# SD_Card_Board.net
KiCad netlist of a schematic drawn in EAGLE
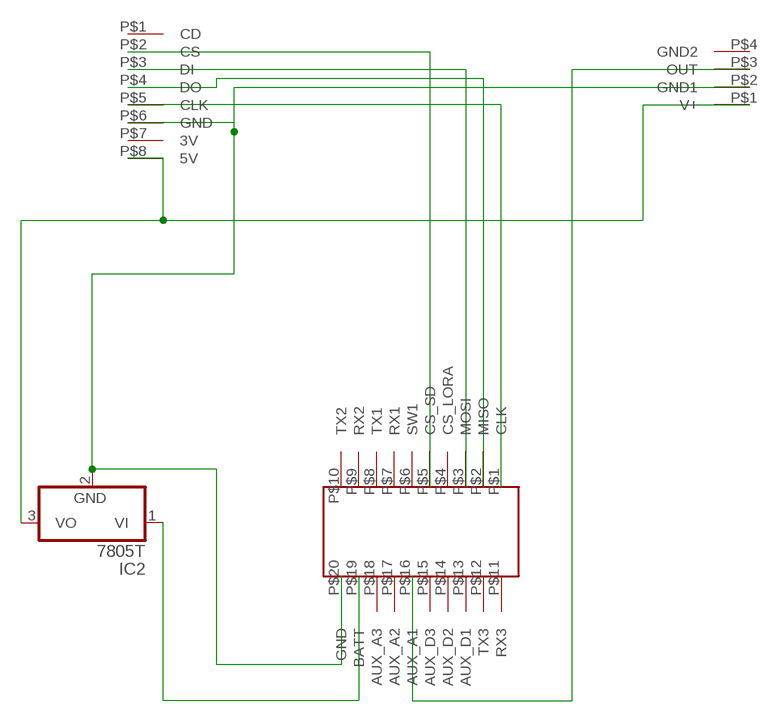
[diagram p0: schematic, sheet 1]

(export (version "E")
  (design (tool "Eeschema 10.0.6"))
  (components
    (comp (ref "IC2")
      (value "7805T")
      (footprint "eagle-import:TO220H")
      (libsource (lib "eagle-import") (part "78T05"))
    )
    (comp (ref "U$1")
      (value "SMALLHEADERPACKAGE")
      (footprint "eagle-import:SMALLHEADERPACKAGE")
      (libsource (lib "eagle-import") (part "SMALLHEADERPACKAGE"))
    )
    (comp (ref "U$2")
      (value "SDCARDREADER")
      (footprint "eagle-import:SDCARDBOARD")
      (libsource (lib "eagle-import") (part "SDCARDREADER"))
    )
    (comp (ref "U$3")
      (value "THERMOCOUPLE")
      (footprint "eagle-import:THERMOBOARD")
      (libsource (lib "eagle-import") (part "THERMOCOUPLE"))
    )
  )
  (nets
    (net (code "1") (name "Net-(IC2-GND)") (class "Default")
      (node (ref "IC2") (pin "2") (pinfunction "GND_2") (pintype "passive"))
      (node (ref "U$1") (pin "P$20") (pinfunction "GND_P$20") (pintype "bidirectional"))
      (node (ref "U$2") (pin "P$6") (pinfunction "GND_P$6") (pintype "bidirectional"))
      (node (ref "U$3") (pin "P$2") (pinfunction "GND1_P$2") (pintype "bidirectional"))
    )
    (net (code "2") (name "Net-(IC2-VI)") (class "Default")
      (node (ref "IC2") (pin "1") (pinfunction "VI_1") (pintype "input"))
      (node (ref "U$1") (pin "P$19") (pinfunction "BATT_P$19") (pintype "bidirectional"))
    )
    (net (code "3") (name "Net-(IC2-VO)") (class "Default")
      (node (ref "IC2") (pin "3") (pinfunction "VO_3") (pintype "passive"))
      (node (ref "U$2") (pin "P$8") (pinfunction "5V_P$8") (pintype "bidirectional"))
      (node (ref "U$3") (pin "P$1") (pinfunction "V+_P$1") (pintype "bidirectional"))
    )
    (net (code "4") (name "Net-(U$1-AUX_A1)") (class "Default")
      (node (ref "U$1") (pin "P$16") (pinfunction "AUX_A1_P$16") (pintype "bidirectional"))
      (node (ref "U$3") (pin "P$3") (pinfunction "OUT_P$3") (pintype "bidirectional"))
    )
    (net (code "5") (name "Net-(U$1-CLK)") (class "Default")
      (node (ref "U$1") (pin "P$1") (pinfunction "CLK_P$1") (pintype "bidirectional"))
      (node (ref "U$2") (pin "P$5") (pinfunction "CLK_P$5") (pintype "bidirectional"))
    )
    (net (code "6") (name "Net-(U$1-CS_SD)") (class "Default")
      (node (ref "U$1") (pin "P$5") (pinfunction "CS_SD_P$5") (pintype "bidirectional"))
      (node (ref "U$2") (pin "P$2") (pinfunction "CS_P$2") (pintype "bidirectional"))
    )
    (net (code "7") (name "Net-(U$1-MISO)") (class "Default")
      (node (ref "U$1") (pin "P$2") (pinfunction "MISO_P$2") (pintype "bidirectional"))
      (node (ref "U$2") (pin "P$4") (pinfunction "DO_P$4") (pintype "bidirectional"))
    )
    (net (code "8") (name "Net-(U$1-MOSI)") (class "Default")
      (node (ref "U$1") (pin "P$3") (pinfunction "MOSI_P$3") (pintype "bidirectional"))
      (node (ref "U$2") (pin "P$3") (pinfunction "DI_P$3") (pintype "bidirectional"))
    )
    (net (code "9") (name "unconnected-(U$1-AUX_A2-PadP$17)") (class "Default")
      (node (ref "U$1") (pin "P$17") (pinfunction "AUX_A2_P$17") (pintype "bidirectional"))
    )
    (net (code "10") (name "unconnected-(U$1-AUX_A3-PadP$18)") (class "Default")
      (node (ref "U$1") (pin "P$18") (pinfunction "AUX_A3_P$18") (pintype "bidirectional"))
    )
    (net (code "11") (name "unconnected-(U$1-AUX_D1-PadP$13)") (class "Default")
      (node (ref "U$1") (pin "P$13") (pinfunction "AUX_D1_P$13") (pintype "bidirectional"))
    )
    (net (code "12") (name "unconnected-(U$1-AUX_D2-PadP$14)") (class "Default")
      (node (ref "U$1") (pin "P$14") (pinfunction "AUX_D2_P$14") (pintype "bidirectional"))
    )
    (net (code "13") (name "unconnected-(U$1-AUX_D3-PadP$15)") (class "Default")
      (node (ref "U$1") (pin "P$15") (pinfunction "AUX_D3_P$15") (pintype "bidirectional"))
    )
    (net (code "14") (name "unconnected-(U$1-CS_LORA-PadP$4)") (class "Default")
      (node (ref "U$1") (pin "P$4") (pinfunction "CS_LORA_P$4") (pintype "bidirectional"))
    )
    (net (code "15") (name "unconnected-(U$1-RX1-PadP$7)") (class "Default")
      (node (ref "U$1") (pin "P$7") (pinfunction "RX1_P$7") (pintype "bidirectional"))
    )
    (net (code "16") (name "unconnected-(U$1-RX2-PadP$9)") (class "Default")
      (node (ref "U$1") (pin "P$9") (pinfunction "RX2_P$9") (pintype "bidirectional"))
    )
    (net (code "17") (name "unconnected-(U$1-RX3-PadP$11)") (class "Default")
      (node (ref "U$1") (pin "P$11") (pinfunction "RX3_P$11") (pintype "bidirectional"))
    )
    (net (code "18") (name "unconnected-(U$1-SW1-PadP$6)") (class "Default")
      (node (ref "U$1") (pin "P$6") (pinfunction "SW1_P$6") (pintype "bidirectional"))
    )
    (net (code "19") (name "unconnected-(U$1-TX1-PadP$8)") (class "Default")
      (node (ref "U$1") (pin "P$8") (pinfunction "TX1_P$8") (pintype "bidirectional"))
    )
    (net (code "20") (name "unconnected-(U$1-TX2-PadP$10)") (class "Default")
      (node (ref "U$1") (pin "P$10") (pinfunction "TX2_P$10") (pintype "bidirectional"))
    )
    (net (code "21") (name "unconnected-(U$1-TX3-PadP$12)") (class "Default")
      (node (ref "U$1") (pin "P$12") (pinfunction "TX3_P$12") (pintype "bidirectional"))
    )
    (net (code "22") (name "unconnected-(U$2-3V-PadP$7)") (class "Default")
      (node (ref "U$2") (pin "P$7") (pinfunction "3V_P$7") (pintype "bidirectional"))
    )
    (net (code "23") (name "unconnected-(U$2-CD-PadP$1)") (class "Default")
      (node (ref "U$2") (pin "P$1") (pinfunction "CD_P$1") (pintype "bidirectional"))
    )
    (net (code "24") (name "unconnected-(U$3-GND2-PadP$4)") (class "Default")
      (node (ref "U$3") (pin "P$4") (pinfunction "GND2_P$4") (pintype "bidirectional"))
    )
  )
)
